# nabijecka_pb.net
KiCad netlist of a schematic drawn in EAGLE
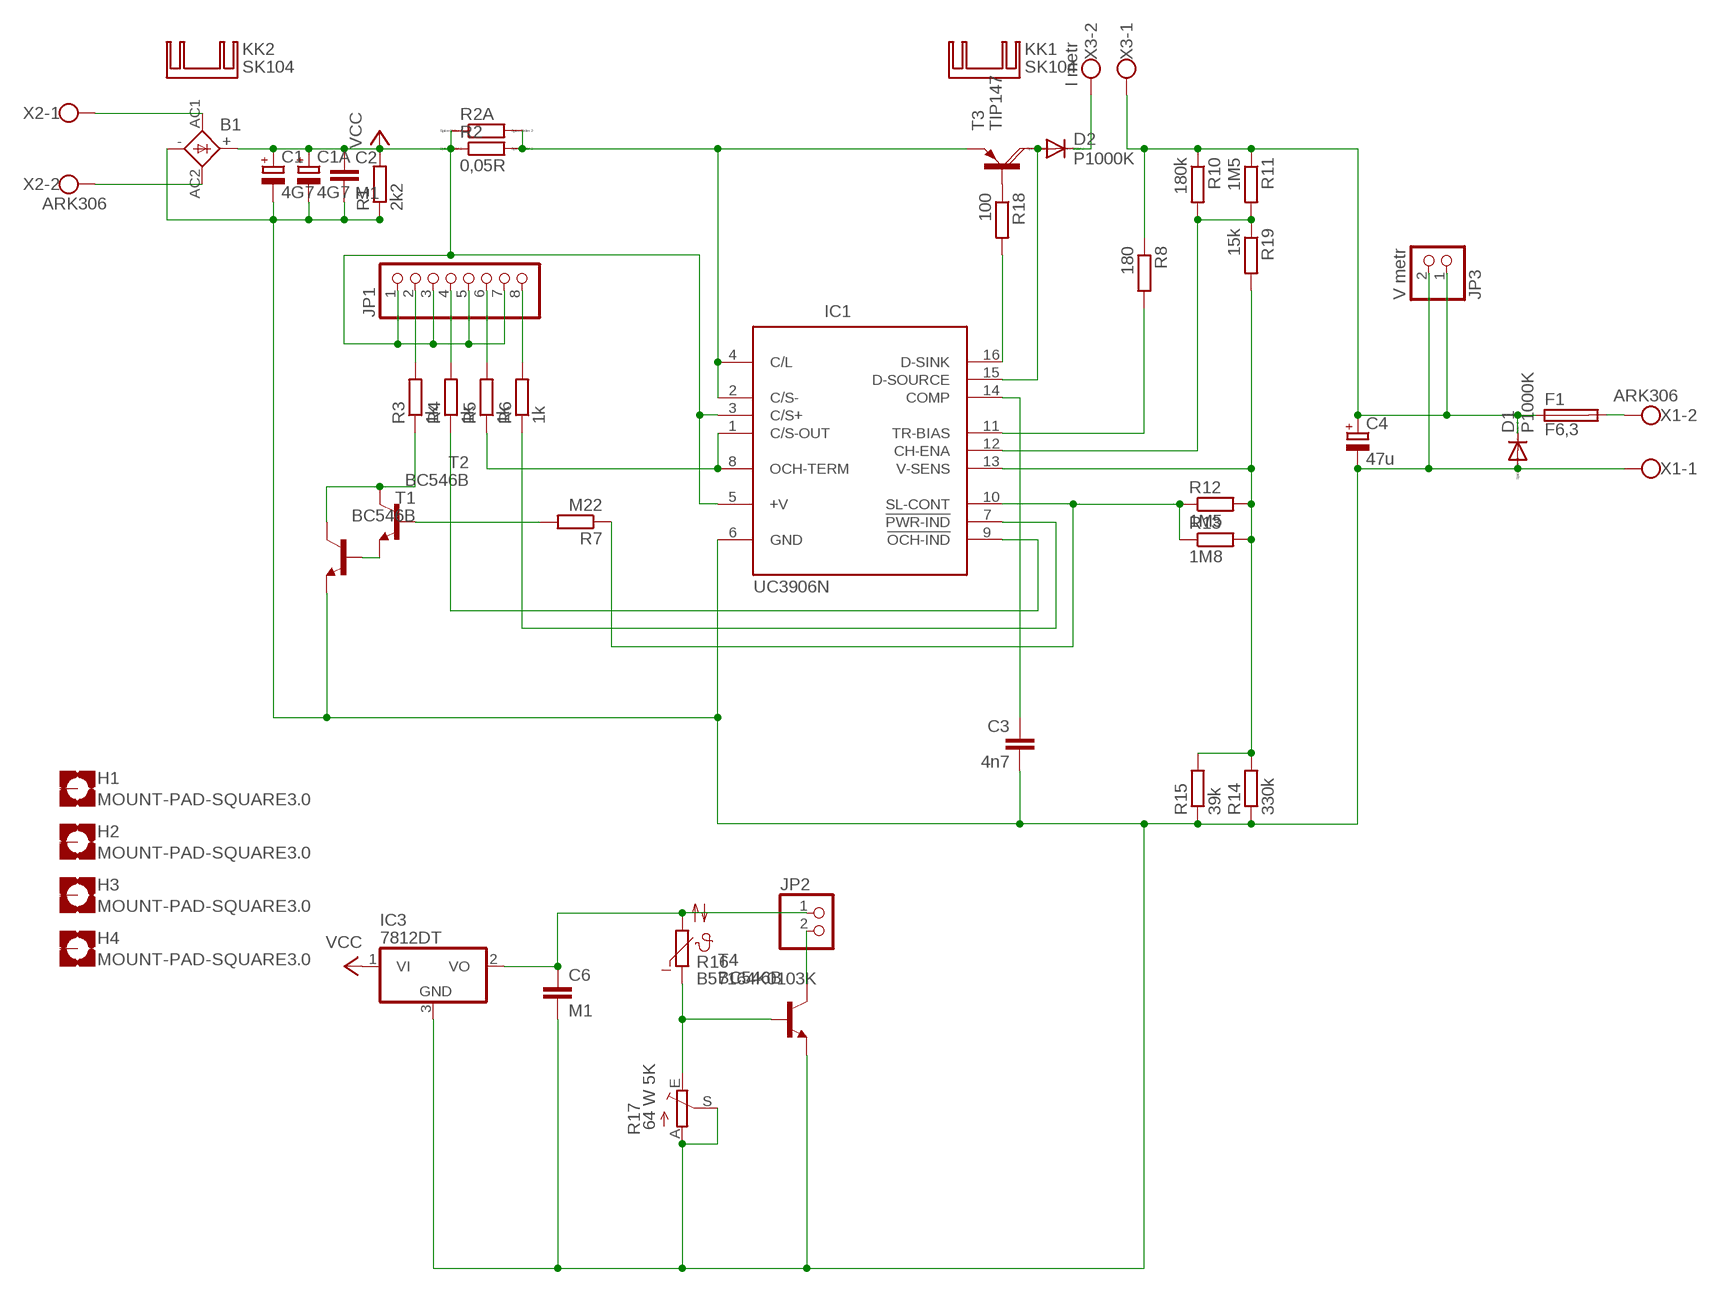
[diagram p0: schematic, sheet 1]

(export (version "E")
  (design (tool "Eeschema 10.0.6"))
  (components
    (comp (ref "B1")
      (value "FB32")
      (footprint "eagle-import:FB32")
      (libsource (lib "eagle-import") (part "FB32"))
    )
    (comp (ref "C1")
      (value "4G7")
      (footprint "eagle-import:E7,5-18")
      (libsource (lib "eagle-import") (part "CPOL-EUE7.5-18"))
    )
    (comp (ref "C1A")
      (value "4G7")
      (footprint "eagle-import:E7,5-18")
      (libsource (lib "eagle-import") (part "CPOL-EUE7.5-18"))
    )
    (comp (ref "C2")
      (value "M1")
      (footprint "eagle-import:C050-045X075")
      (libsource (lib "eagle-import") (part "C-EU050-045X075"))
    )
    (comp (ref "C3")
      (value "4n7")
      (footprint "eagle-import:C050-045X075")
      (libsource (lib "eagle-import") (part "C-EU050-045X075"))
    )
    (comp (ref "C4")
      (value "47u")
      (footprint "eagle-import:E2,5-6")
      (libsource (lib "eagle-import") (part "CPOL-EUE2.5-6"))
    )
    (comp (ref "C6")
      (value "M1")
      (footprint "eagle-import:C1206")
      (libsource (lib "eagle-import") (part "C-EUC1206"))
    )
    (comp (ref "D1")
      (value "P1000K")
      (footprint "eagle-import:P6-15")
      (libsource (lib "eagle-import") (part "P600"))
    )
    (comp (ref "D2")
      (value "P1000K")
      (footprint "eagle-import:P6-15")
      (libsource (lib "eagle-import") (part "P600"))
    )
    (comp (ref "F1")
      (value "F6,3")
      (footprint "eagle-import:F456")
      (libsource (lib "eagle-import") (part "FUSEF456"))
    )
    (comp (ref "H1")
      (value "MOUNT-PAD-SQUARE3.0")
      (footprint "eagle-import:3,0-PAD-SQUARE")
      (libsource (lib "eagle-import") (part "MOUNT-PAD-SQUARE3.0"))
    )
    (comp (ref "H2")
      (value "MOUNT-PAD-SQUARE3.0")
      (footprint "eagle-import:3,0-PAD-SQUARE")
      (libsource (lib "eagle-import") (part "MOUNT-PAD-SQUARE3.0"))
    )
    (comp (ref "H3")
      (value "MOUNT-PAD-SQUARE3.0")
      (footprint "eagle-import:3,0-PAD-SQUARE")
      (libsource (lib "eagle-import") (part "MOUNT-PAD-SQUARE3.0"))
    )
    (comp (ref "H4")
      (value "MOUNT-PAD-SQUARE3.0")
      (footprint "eagle-import:3,0-PAD-SQUARE")
      (libsource (lib "eagle-import") (part "MOUNT-PAD-SQUARE3.0"))
    )
    (comp (ref "IC1")
      (value "UC3906N")
      (footprint "eagle-import:DIL16")
      (libsource (lib "eagle-import") (part "UC3906N"))
    )
    (comp (ref "IC3")
      (value "7812DT")
      (footprint "eagle-import:TO252")
      (libsource (lib "eagle-import") (part "78DT12"))
    )
    (comp (ref "JP1")
      (value "PINHD-1X8")
      (footprint "eagle-import:1X08")
      (libsource (lib "eagle-import") (part "PINHD-1X8"))
    )
    (comp (ref "JP2")
      (value "PINHD-1X2")
      (footprint "eagle-import:1X02")
      (libsource (lib "eagle-import") (part "PINHD-1X2"))
    )
    (comp (ref "JP3")
      (value "V metr")
      (footprint "eagle-import:1X02")
      (libsource (lib "eagle-import") (part "PINHD-1X2"))
    )
    (comp (ref "KK1")
      (value "SK104")
      (footprint "eagle-import:SK104")
      (libsource (lib "eagle-import") (part "SK104"))
    )
    (comp (ref "KK2")
      (value "SK104")
      (footprint "eagle-import:SK104")
      (libsource (lib "eagle-import") (part "SK104"))
    )
    (comp (ref "R1")
      (value "2k2")
      (footprint "eagle-import:0207_10")
      (libsource (lib "eagle-import") (part "R-EU_0207/10"))
    )
    (comp (ref "R2")
      (value "0,05R")
      (footprint "eagle-import:P0817_22")
      (libsource (lib "eagle-import") (part "R-EU_0817_22"))
    )
    (comp (ref "R2A")
      (value "R-EU_0817_22")
      (footprint "eagle-import:P0817_22")
      (libsource (lib "eagle-import") (part "R-EU_0817_22"))
    )
    (comp (ref "R3")
      (value "1k")
      (footprint "eagle-import:0207_10")
      (libsource (lib "eagle-import") (part "R-EU_0207/10"))
    )
    (comp (ref "R4")
      (value "1k")
      (footprint "eagle-import:0207_10")
      (libsource (lib "eagle-import") (part "R-EU_0207/10"))
    )
    (comp (ref "R5")
      (value "1k")
      (footprint "eagle-import:0207_10")
      (libsource (lib "eagle-import") (part "R-EU_0207/10"))
    )
    (comp (ref "R6")
      (value "1k")
      (footprint "eagle-import:0207_10")
      (libsource (lib "eagle-import") (part "R-EU_0207/10"))
    )
    (comp (ref "R7")
      (value "M22")
      (footprint "eagle-import:0207_10")
      (libsource (lib "eagle-import") (part "R-EU_0207/10"))
    )
    (comp (ref "R8")
      (value "180")
      (footprint "eagle-import:0207_10")
      (libsource (lib "eagle-import") (part "R-EU_0207/10"))
    )
    (comp (ref "R10")
      (value "180k")
      (footprint "eagle-import:0207_10")
      (libsource (lib "eagle-import") (part "R-EU_0207/10"))
    )
    (comp (ref "R11")
      (value "1M5")
      (footprint "eagle-import:0207_10")
      (libsource (lib "eagle-import") (part "R-EU_0207/10"))
    )
    (comp (ref "R12")
      (value "1M5")
      (footprint "eagle-import:0207_10")
      (libsource (lib "eagle-import") (part "R-EU_0207/10"))
    )
    (comp (ref "R13")
      (value "1M8")
      (footprint "eagle-import:0207_10")
      (libsource (lib "eagle-import") (part "R-EU_0207/10"))
    )
    (comp (ref "R14")
      (value "330k")
      (footprint "eagle-import:0207_10")
      (libsource (lib "eagle-import") (part "R-EU_0207/10"))
    )
    (comp (ref "R15")
      (value "39k")
      (footprint "eagle-import:0207_10")
      (libsource (lib "eagle-import") (part "R-EU_0207/10"))
    )
    (comp (ref "R16")
      (value "B57164K0103K")
      (footprint "eagle-import:P642")
      (libsource (lib "eagle-import") (part "NTC642-6"))
    )
    (comp (ref "R17")
      (value "64 W 5K")
      (footprint "eagle-import:S64W")
      (libsource (lib "eagle-import") (part "TRIM_EU-S64W"))
    )
    (comp (ref "R18")
      (value "100")
      (footprint "eagle-import:0207_10")
      (libsource (lib "eagle-import") (part "R-EU_0207/10"))
    )
    (comp (ref "R19")
      (value "15k")
      (footprint "eagle-import:0207_10")
      (libsource (lib "eagle-import") (part "R-EU_0207/10"))
    )
    (comp (ref "T1")
      (value "BC546B")
      (footprint "eagle-import:TO92-EBC")
      (libsource (lib "eagle-import") (part "BC546B"))
    )
    (comp (ref "T2")
      (value "BC546B")
      (footprint "eagle-import:TO92-EBC")
      (libsource (lib "eagle-import") (part "BC546B"))
    )
    (comp (ref "T3")
      (value "TIP147")
      (footprint "eagle-import:SOT93")
      (libsource (lib "eagle-import") (part "TIP147"))
    )
    (comp (ref "T4")
      (value "BC546B")
      (footprint "eagle-import:TO92-EBC")
      (libsource (lib "eagle-import") (part "BC546B"))
    )
    (comp (ref "X1")
      (value "ARK306")
      (footprint "eagle-import:W237-102")
      (fields (field (name "MPN") "237-102"))
      (libsource (lib "eagle-import") (part "W237-102"))
    )
    (comp (ref "X2")
      (value "ARK306")
      (footprint "eagle-import:W237-102")
      (fields (field (name "MPN") "237-102"))
      (libsource (lib "eagle-import") (part "W237-102"))
    )
    (comp (ref "X3")
      (value "I metr")
      (footprint "eagle-import:W237-102")
      (fields (field (name "MPN") "237-102"))
      (libsource (lib "eagle-import") (part "W237-102"))
    )
  )
  (nets
    (net (code "1") (name "Net-(IC1-CH-ENA)") (class "Default")
      (node (ref "IC1") (pin "12") (pinfunction "CH-ENA_12") (pintype "input"))
      (node (ref "R10") (pin "2") (pinfunction "2_2") (pintype "passive"))
      (node (ref "R11") (pin "2") (pinfunction "2_2") (pintype "passive"))
      (node (ref "R19") (pin "1") (pinfunction "1_1") (pintype "passive"))
    )
    (net (code "2") (name "Net-(IC1-COMP)") (class "Default")
      (node (ref "C3") (pin "1") (pinfunction "1_1") (pintype "passive"))
      (node (ref "IC1") (pin "14") (pinfunction "COMP_14") (pintype "passive"))
    )
    (net (code "3") (name "Net-(IC1-C{slash}L)") (class "Default")
      (node (ref "IC1") (pin "2") (pinfunction "C/S-_2") (pintype "input"))
      (node (ref "IC1") (pin "4") (pinfunction "C/L_4") (pintype "input"))
      (node (ref "R2") (pin "2") (pinfunction "2_2") (pintype "passive"))
      (node (ref "R2A") (pin "2") (pinfunction "2_2") (pintype "passive"))
      (node (ref "T3") (pin "E") (pinfunction "E_E") (pintype "passive"))
    )
    (net (code "4") (name "Net-(IC1-C{slash}S-OUT)") (class "Default")
      (node (ref "IC1") (pin "1") (pinfunction "C/S-OUT_1") (pintype "open_collector"))
      (node (ref "IC1") (pin "8") (pinfunction "OCH-TERM_8") (pintype "input"))
      (node (ref "R5") (pin "1") (pinfunction "1_1") (pintype "passive"))
    )
    (net (code "5") (name "Net-(IC1-D-SINK)") (class "Default")
      (node (ref "IC1") (pin "16") (pinfunction "D-SINK_16") (pintype "open_collector"))
      (node (ref "R18") (pin "2") (pinfunction "2_2") (pintype "passive"))
    )
    (net (code "6") (name "Net-(IC1-D-SOURCE)") (class "Default")
      (node (ref "D2") (pin "A") (pinfunction "A_A") (pintype "passive"))
      (node (ref "IC1") (pin "15") (pinfunction "D-SOURCE_15") (pintype "passive"))
      (node (ref "T3") (pin "C") (pinfunction "C_C") (pintype "passive"))
    )
    (net (code "7") (name "Net-(IC1-GND)") (class "Default")
      (node (ref "B1") (pin "-") (pinfunction "-_-") (pintype "passive"))
      (node (ref "C1") (pin "-") (pinfunction "-_-") (pintype "passive"))
      (node (ref "C1A") (pin "-") (pinfunction "-_-") (pintype "passive"))
      (node (ref "C2") (pin "2") (pinfunction "2_2") (pintype "passive"))
      (node (ref "C3") (pin "2") (pinfunction "2_2") (pintype "passive"))
      (node (ref "C4") (pin "-") (pinfunction "-_-") (pintype "passive"))
      (node (ref "C6") (pin "2") (pinfunction "2_2") (pintype "passive"))
      (node (ref "D1") (pin "A") (pinfunction "A_A") (pintype "passive"))
      (node (ref "IC1") (pin "6") (pinfunction "GND_6") (pintype "power_in"))
      (node (ref "IC3") (pin "3") (pinfunction "GND_3") (pintype "passive"))
      (node (ref "JP3") (pin "2") (pinfunction "2_2") (pintype "passive"))
      (node (ref "R1") (pin "1") (pinfunction "1_1") (pintype "passive"))
      (node (ref "R14") (pin "1") (pinfunction "1_1") (pintype "passive"))
      (node (ref "R15") (pin "1") (pinfunction "1_1") (pintype "passive"))
      (node (ref "R17") (pin "A") (pinfunction "A_A") (pintype "passive"))
      (node (ref "R17") (pin "S") (pinfunction "S_S") (pintype "passive"))
      (node (ref "T1") (pin "E") (pinfunction "E_E") (pintype "passive"))
      (node (ref "T4") (pin "E") (pinfunction "E_E") (pintype "passive"))
      (node (ref "X1") (pin "1") (pinfunction "KL_1") (pintype "passive"))
    )
    (net (code "8") (name "Net-(IC1-SL-CONT)") (class "Default")
      (node (ref "IC1") (pin "10") (pinfunction "SL-CONT_10") (pintype "open_collector"))
      (node (ref "R12") (pin "1") (pinfunction "1_1") (pintype "passive"))
      (node (ref "R13") (pin "1") (pinfunction "1_1") (pintype "passive"))
      (node (ref "R7") (pin "1") (pinfunction "1_1") (pintype "passive"))
    )
    (net (code "9") (name "Net-(IC1-TR-BIAS)") (class "Default")
      (node (ref "IC1") (pin "11") (pinfunction "TR-BIAS_11") (pintype "output"))
      (node (ref "R8") (pin "2") (pinfunction "2_2") (pintype "passive"))
    )
    (net (code "10") (name "Net-(IC1-V-SENS)") (class "Default")
      (node (ref "IC1") (pin "13") (pinfunction "V-SENS_13") (pintype "input"))
      (node (ref "R12") (pin "2") (pinfunction "2_2") (pintype "passive"))
      (node (ref "R13") (pin "2") (pinfunction "2_2") (pintype "passive"))
      (node (ref "R14") (pin "2") (pinfunction "2_2") (pintype "passive"))
      (node (ref "R15") (pin "2") (pinfunction "2_2") (pintype "passive"))
      (node (ref "R19") (pin "2") (pinfunction "2_2") (pintype "passive"))
    )
    (net (code "11") (name "Net-(IC1-~{OCH-IND})") (class "Default")
      (node (ref "IC1") (pin "9") (pinfunction "~{OCH-IND}_9") (pintype "open_collector"))
      (node (ref "R4") (pin "1") (pinfunction "1_1") (pintype "passive"))
    )
    (net (code "12") (name "Net-(IC1-~{PWR-IND})") (class "Default")
      (node (ref "IC1") (pin "7") (pinfunction "~{PWR-IND}_7") (pintype "open_collector"))
      (node (ref "R6") (pin "1") (pinfunction "1_1") (pintype "passive"))
    )
    (net (code "13") (name "Net-(IC3-VO)") (class "Default")
      (node (ref "C6") (pin "1") (pinfunction "1_1") (pintype "passive"))
      (node (ref "IC3") (pin "2") (pinfunction "VO_2") (pintype "passive"))
      (node (ref "JP2") (pin "1") (pinfunction "1_1") (pintype "passive"))
      (node (ref "R16") (pin "2") (pinfunction "2_2") (pintype "passive"))
    )
    (net (code "14") (name "Net-(JP1-Pad2)") (class "Default")
      (node (ref "JP1") (pin "2") (pinfunction "2_2") (pintype "passive"))
      (node (ref "R3") (pin "2") (pinfunction "2_2") (pintype "passive"))
    )
    (net (code "15") (name "Net-(JP1-Pad4)") (class "Default")
      (node (ref "JP1") (pin "4") (pinfunction "4_4") (pintype "passive"))
      (node (ref "R4") (pin "2") (pinfunction "2_2") (pintype "passive"))
    )
    (net (code "16") (name "Net-(JP1-Pad6)") (class "Default")
      (node (ref "JP1") (pin "6") (pinfunction "6_6") (pintype "passive"))
      (node (ref "R5") (pin "2") (pinfunction "2_2") (pintype "passive"))
    )
    (net (code "17") (name "Net-(JP1-Pad8)") (class "Default")
      (node (ref "JP1") (pin "8") (pinfunction "8_8") (pintype "passive"))
      (node (ref "R6") (pin "2") (pinfunction "2_2") (pintype "passive"))
    )
    (net (code "18") (name "Net-(JP2-Pad2)") (class "Default")
      (node (ref "JP2") (pin "2") (pinfunction "2_2") (pintype "passive"))
      (node (ref "T4") (pin "C") (pinfunction "C_C") (pintype "passive"))
    )
    (net (code "19") (name "Net-(R3-Pad1)") (class "Default")
      (node (ref "R3") (pin "1") (pinfunction "1_1") (pintype "passive"))
      (node (ref "T1") (pin "C") (pinfunction "C_C") (pintype "passive"))
      (node (ref "T2") (pin "C") (pinfunction "C_C") (pintype "passive"))
    )
    (net (code "20") (name "Net-(R7-Pad2)") (class "Default")
      (node (ref "R7") (pin "2") (pinfunction "2_2") (pintype "passive"))
      (node (ref "T2") (pin "B") (pinfunction "B_B") (pintype "passive"))
    )
    (net (code "21") (name "Net-(R16-Pad1)") (class "Default")
      (node (ref "R16") (pin "1") (pinfunction "1_1") (pintype "passive"))
      (node (ref "R17") (pin "E") (pinfunction "E_E") (pintype "passive"))
      (node (ref "T4") (pin "B") (pinfunction "B_B") (pintype "passive"))
    )
    (net (code "22") (name "Net-(R18-Pad1)") (class "Default")
      (node (ref "R18") (pin "1") (pinfunction "1_1") (pintype "passive"))
      (node (ref "T3") (pin "B") (pinfunction "B_B") (pintype "passive"))
    )
    (net (code "23") (name "Net-(T1-PadB)") (class "Default")
      (node (ref "T1") (pin "B") (pinfunction "B_B") (pintype "passive"))
      (node (ref "T2") (pin "E") (pinfunction "E_E") (pintype "passive"))
    )
    (net (code "24") (name "Net-(X1B-KL)") (class "Default")
      (node (ref "F1") (pin "2") (pinfunction "2_2") (pintype "passive"))
      (node (ref "X1") (pin "2") (pinfunction "KL_2") (pintype "passive"))
    )
    (net (code "25") (name "Net-(X2A-KL)") (class "Default")
      (node (ref "B1") (pin "AC1") (pinfunction "AC1_AC1") (pintype "passive"))
      (node (ref "X2") (pin "1") (pinfunction "KL_1") (pintype "passive"))
    )
    (net (code "26") (name "Net-(X2B-KL)") (class "Default")
      (node (ref "B1") (pin "AC2") (pinfunction "AC2_AC2") (pintype "passive"))
      (node (ref "X2") (pin "2") (pinfunction "KL_2") (pintype "passive"))
    )
    (net (code "27") (name "Net-(X3A-KL)") (class "Default")
      (node (ref "C4") (pin "+") (pinfunction "+_+") (pintype "passive"))
      (node (ref "D1") (pin "C") (pinfunction "C_C") (pintype "passive"))
      (node (ref "F1") (pin "1") (pinfunction "1_1") (pintype "passive"))
      (node (ref "JP3") (pin "1") (pinfunction "1_1") (pintype "passive"))
      (node (ref "R10") (pin "1") (pinfunction "1_1") (pintype "passive"))
      (node (ref "R11") (pin "1") (pinfunction "1_1") (pintype "passive"))
      (node (ref "R8") (pin "1") (pinfunction "1_1") (pintype "passive"))
      (node (ref "X3") (pin "1") (pinfunction "KL_1") (pintype "passive"))
    )
    (net (code "28") (name "Net-(X3B-KL)") (class "Default")
      (node (ref "D2") (pin "C") (pinfunction "C_C") (pintype "passive"))
      (node (ref "X3") (pin "2") (pinfunction "KL_2") (pintype "passive"))
    )
    (net (code "29") (name "VCC") (class "Default")
      (node (ref "B1") (pin "+") (pinfunction "+_+") (pintype "passive"))
      (node (ref "C1") (pin "+") (pinfunction "+_+") (pintype "passive"))
      (node (ref "C1A") (pin "+") (pinfunction "+_+") (pintype "passive"))
      (node (ref "C2") (pin "1") (pinfunction "1_1") (pintype "passive"))
      (node (ref "IC1") (pin "3") (pinfunction "C/S+_3") (pintype "input"))
      (node (ref "IC1") (pin "5") (pinfunction "+V_5") (pintype "power_in"))
      (node (ref "IC3") (pin "1") (pinfunction "VI_1") (pintype "input"))
      (node (ref "JP1") (pin "1") (pinfunction "1_1") (pintype "passive"))
      (node (ref "JP1") (pin "3") (pinfunction "3_3") (pintype "passive"))
      (node (ref "JP1") (pin "5") (pinfunction "5_5") (pintype "passive"))
      (node (ref "JP1") (pin "7") (pinfunction "7_7") (pintype "passive"))
      (node (ref "R1") (pin "2") (pinfunction "2_2") (pintype "passive"))
      (node (ref "R2") (pin "1") (pinfunction "1_1") (pintype "passive"))
      (node (ref "R2A") (pin "1") (pinfunction "1_1") (pintype "passive"))
    )
    (net (code "30") (name "unconnected-(H1-MOUNT-PadB3,0)") (class "Default")
      (node (ref "H1") (pin "B3,0") (pinfunction "MOUNT_B3,0") (pintype "passive"))
    )
    (net (code "31") (name "unconnected-(H2-MOUNT-PadB3,0)") (class "Default")
      (node (ref "H2") (pin "B3,0") (pinfunction "MOUNT_B3,0") (pintype "passive"))
    )
    (net (code "32") (name "unconnected-(H3-MOUNT-PadB3,0)") (class "Default")
      (node (ref "H3") (pin "B3,0") (pinfunction "MOUNT_B3,0") (pintype "passive"))
    )
    (net (code "33") (name "unconnected-(H4-MOUNT-PadB3,0)") (class "Default")
      (node (ref "H4") (pin "B3,0") (pinfunction "MOUNT_B3,0") (pintype "passive"))
    )
  )
)
